# Vsense.net
KiCad netlist of a schematic drawn in Altium Designer
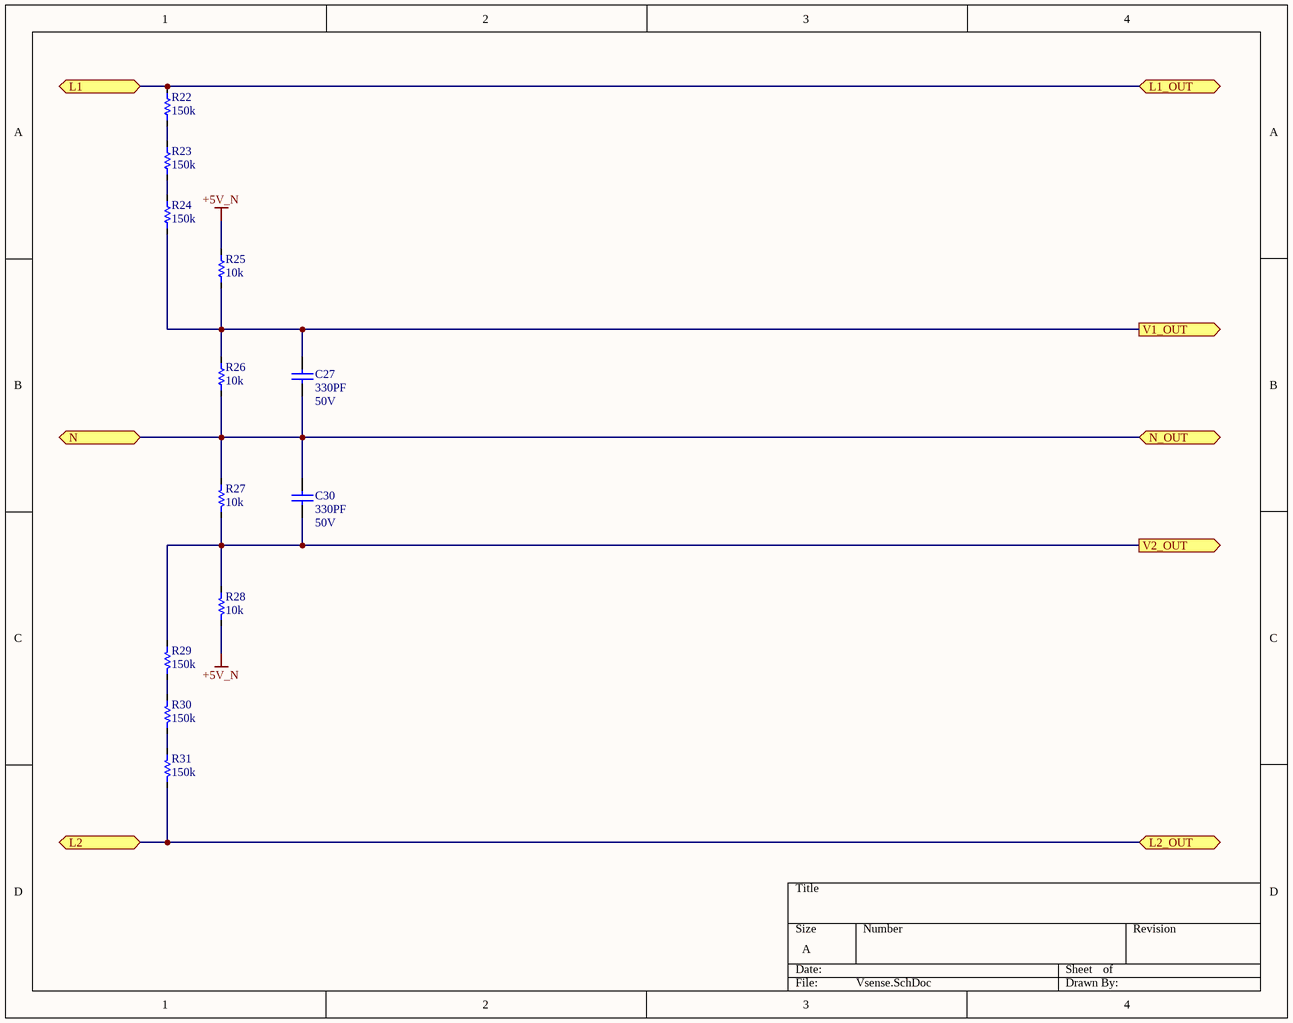
[diagram p0: Vsense.SchDoc]

(export (version "E")
  (design (tool "Eeschema 10.0.6"))
  (components
    (comp (ref "C27")
      (value "GRM188R71H331KA01D")
      (footprint "CAPC1608X08N")
      (description "CAP CER 330PF 50V X7R 0603")
      (fields
        (field (name "MANUFACTURER") "Murata Electronics North America")
        (field (name "CAPACITANCE") "330PF")
        (field (name "VOLTAGE - RATED") "50V")
      )
      (libsource (lib "IntelligentJunctionBox") (part "GRM188R71H331KA01D"))
    )
    (comp (ref "C30")
      (value "GRM188R71H331KA01D")
      (footprint "CAPC1608X08N")
      (description "CAP CER 330PF 50V X7R 0603")
      (fields
        (field (name "MANUFACTURER") "Murata Electronics North America")
        (field (name "CAPACITANCE") "330PF")
        (field (name "VOLTAGE - RATED") "50V")
      )
      (libsource (lib "IntelligentJunctionBox") (part "GRM188R71H331KA01D"))
    )
    (comp (ref "R22")
      (value "RC0805FR-07150KL")
      (footprint "RESC2012X06N")
      (description "RES SMD 150K OHM 1% 1/8W 0805")
      (fields (field (name "MANUFACTURER") "Yageo") (field (name "RESISTANCE") "150k"))
      (libsource (lib "IntelligentJunctionBox") (part "RC0805FR-07150KL"))
    )
    (comp (ref "R23")
      (value "RC0805FR-07150KL")
      (footprint "RESC2012X06N")
      (description "RES SMD 150K OHM 1% 1/8W 0805")
      (fields (field (name "MANUFACTURER") "Yageo") (field (name "RESISTANCE") "150k"))
      (libsource (lib "IntelligentJunctionBox") (part "RC0805FR-07150KL"))
    )
    (comp (ref "R24")
      (value "RC0805FR-07150KL")
      (footprint "RESC2012X06N")
      (description "RES SMD 150K OHM 1% 1/8W 0805")
      (fields (field (name "MANUFACTURER") "Yageo") (field (name "RESISTANCE") "150k"))
      (libsource (lib "IntelligentJunctionBox") (part "RC0805FR-07150KL"))
    )
    (comp (ref "R25")
      (value "RC0603FR-0710KL")
      (footprint "RESC1608X06N")
      (description "RES SMD 10K OHM 1% 1/10W 0603")
      (fields (field (name "MANUFACTURER") "Yageo") (field (name "RESISTANCE") "10k"))
      (libsource (lib "IntelligentJunctionBox") (part "RC0603FR-0710KL"))
    )
    (comp (ref "R26")
      (value "RC0603FR-0710KL")
      (footprint "RESC1608X06N")
      (description "RES SMD 10K OHM 1% 1/10W 0603")
      (fields (field (name "MANUFACTURER") "Yageo") (field (name "RESISTANCE") "10k"))
      (libsource (lib "IntelligentJunctionBox") (part "RC0603FR-0710KL"))
    )
    (comp (ref "R27")
      (value "RC0603FR-0710KL")
      (footprint "RESC1608X06N")
      (description "RES SMD 10K OHM 1% 1/10W 0603")
      (fields (field (name "MANUFACTURER") "Yageo") (field (name "RESISTANCE") "10k"))
      (libsource (lib "IntelligentJunctionBox") (part "RC0603FR-0710KL"))
    )
    (comp (ref "R28")
      (value "RC0603FR-0710KL")
      (footprint "RESC1608X06N")
      (description "RES SMD 10K OHM 1% 1/10W 0603")
      (fields (field (name "MANUFACTURER") "Yageo") (field (name "RESISTANCE") "10k"))
      (libsource (lib "IntelligentJunctionBox") (part "RC0603FR-0710KL"))
    )
    (comp (ref "R29")
      (value "RC0805FR-07150KL")
      (footprint "RESC2012X06N")
      (description "RES SMD 150K OHM 1% 1/8W 0805")
      (fields (field (name "MANUFACTURER") "Yageo") (field (name "RESISTANCE") "150k"))
      (libsource (lib "IntelligentJunctionBox") (part "RC0805FR-07150KL"))
    )
    (comp (ref "R30")
      (value "RC0805FR-07150KL")
      (footprint "RESC2012X06N")
      (description "RES SMD 150K OHM 1% 1/8W 0805")
      (fields (field (name "MANUFACTURER") "Yageo") (field (name "RESISTANCE") "150k"))
      (libsource (lib "IntelligentJunctionBox") (part "RC0805FR-07150KL"))
    )
    (comp (ref "R31")
      (value "RC0805FR-07150KL")
      (footprint "RESC2012X06N")
      (description "RES SMD 150K OHM 1% 1/8W 0805")
      (fields (field (name "MANUFACTURER") "Yageo") (field (name "RESISTANCE") "150k"))
      (libsource (lib "IntelligentJunctionBox") (part "RC0805FR-07150KL"))
    )
  )
  (nets
    (net (code "1") (name "+5V_N") (class "Default")
      (node (ref "R25") (pin "2") (pinfunction "2_2") (pintype "passive"))
      (node (ref "R28") (pin "2") (pinfunction "2_2") (pintype "passive"))
    )
    (net (code "2") (name "/L1") (class "Default")
      (node (ref "R22") (pin "2") (pinfunction "2_2") (pintype "passive"))
    )
    (net (code "3") (name "/L2") (class "Default")
      (node (ref "R31") (pin "2") (pinfunction "2_2") (pintype "passive"))
    )
    (net (code "4") (name "/N") (class "Default")
      (node (ref "C27") (pin "1") (pinfunction "1_1") (pintype "passive"))
      (node (ref "C30") (pin "2") (pinfunction "2_2") (pintype "passive"))
      (node (ref "R26") (pin "1") (pinfunction "1_1") (pintype "passive"))
      (node (ref "R27") (pin "1") (pinfunction "1_1") (pintype "passive"))
    )
    (net (code "5") (name "/V1_OUT") (class "Default")
      (node (ref "C27") (pin "2") (pinfunction "2_2") (pintype "passive"))
      (node (ref "R24") (pin "1") (pinfunction "1_1") (pintype "passive"))
      (node (ref "R25") (pin "1") (pinfunction "1_1") (pintype "passive"))
      (node (ref "R26") (pin "2") (pinfunction "2_2") (pintype "passive"))
    )
    (net (code "6") (name "/V2_OUT") (class "Default")
      (node (ref "C30") (pin "1") (pinfunction "1_1") (pintype "passive"))
      (node (ref "R27") (pin "2") (pinfunction "2_2") (pintype "passive"))
      (node (ref "R28") (pin "1") (pinfunction "1_1") (pintype "passive"))
      (node (ref "R29") (pin "1") (pinfunction "1_1") (pintype "passive"))
    )
    (net (code "7") (name "Net-(R22-Pad1)") (class "Default")
      (node (ref "R22") (pin "1") (pinfunction "1_1") (pintype "passive"))
      (node (ref "R23") (pin "2") (pinfunction "2_2") (pintype "passive"))
    )
    (net (code "8") (name "Net-(R23-Pad1)") (class "Default")
      (node (ref "R23") (pin "1") (pinfunction "1_1") (pintype "passive"))
      (node (ref "R24") (pin "2") (pinfunction "2_2") (pintype "passive"))
    )
    (net (code "9") (name "Net-(R29-Pad2)") (class "Default")
      (node (ref "R29") (pin "2") (pinfunction "2_2") (pintype "passive"))
      (node (ref "R30") (pin "1") (pinfunction "1_1") (pintype "passive"))
    )
    (net (code "10") (name "Net-(R30-Pad2)") (class "Default")
      (node (ref "R30") (pin "2") (pinfunction "2_2") (pintype "passive"))
      (node (ref "R31") (pin "1") (pinfunction "1_1") (pintype "passive"))
    )
  )
)
